# STN1170_RN-42_CPU_Rev2.net
KiCad netlist of a schematic drawn in Altium Designer
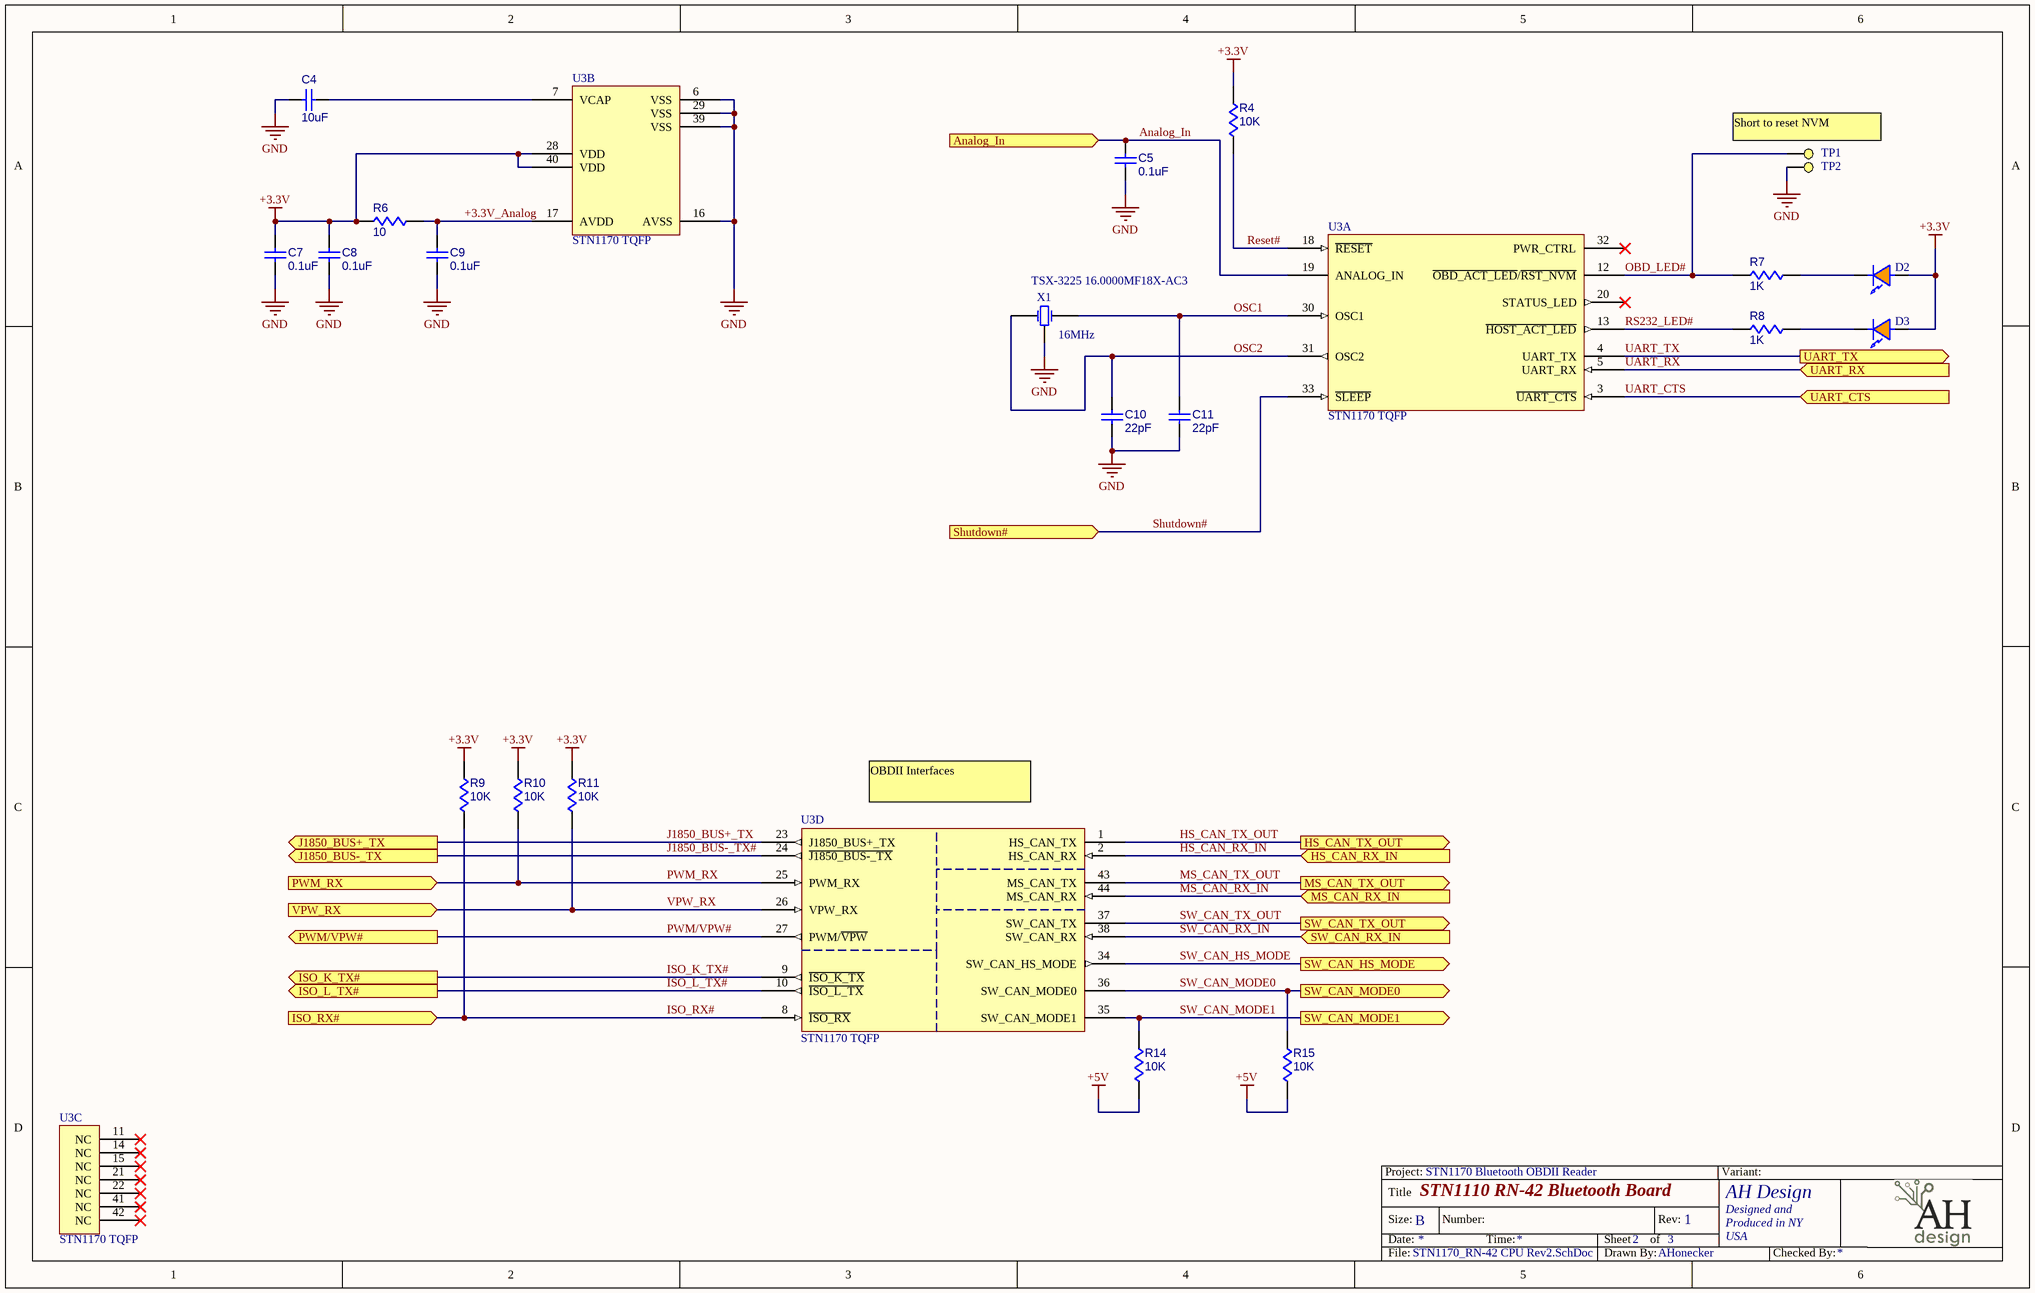
[diagram p0: STN1170_RN-42 CPU Rev2.SchDoc]

(export (version "E")
  (design (tool "Eeschema 10.0.6"))
  (components
    (comp (ref "C4")
      (value "10uF")
      (footprint "CC0805")
      (description "10uF 6.3V, in a CC0805, X5R ,+/-20%,LF")
      (fields
        (field (name "VOLTAGE") "6.3")
        (field (name "MANUFACTURER") "Kemet Electronics Corp")
        (field (name "PUBLISHER") "AltiumDBManager1.4-MWyman")
        (field (name "APPROVED") "Yes")
        (field (name "APPROVER") "IHS")
      )
      (libsource (lib "VanteonStd") (part "CAP"))
    )
    (comp (ref "C5")
      (value "0.1uF")
      (footprint "CC0603")
      (description "0.1uF 50V, in a CC0603, X7R ,+/-20%,LF")
      (fields
        (field (name "VOLTAGE") "50")
        (field (name "MANUFACTURER") "Kemet")
        (field (name "PUBLISHER") "AltiumdBManager")
        (field (name "APPROVED") "Pending")
      )
      (libsource (lib "VanteonStd") (part "CAP"))
    )
    (comp (ref "C7")
      (value "0.1uF")
      (footprint "CC0603")
      (description "0.1uF 50V, in a CC0603, X7R ,+/-20%,LF")
      (fields
        (field (name "VOLTAGE") "50")
        (field (name "MANUFACTURER") "Kemet")
        (field (name "PUBLISHER") "AltiumdBManager")
        (field (name "APPROVED") "Pending")
      )
      (libsource (lib "VanteonStd") (part "CAP"))
    )
    (comp (ref "C8")
      (value "0.1uF")
      (footprint "CC0603")
      (description "0.1uF 50V, in a CC0603, X7R ,+/-20%,LF")
      (fields
        (field (name "VOLTAGE") "50")
        (field (name "MANUFACTURER") "Kemet")
        (field (name "PUBLISHER") "AltiumdBManager")
        (field (name "APPROVED") "Pending")
      )
      (libsource (lib "VanteonStd") (part "CAP"))
    )
    (comp (ref "C9")
      (value "0.1uF")
      (footprint "CC0603")
      (description "0.1uF 50V, in a CC0603, X7R ,+/-20%,LF")
      (fields
        (field (name "VOLTAGE") "50")
        (field (name "MANUFACTURER") "Kemet")
        (field (name "PUBLISHER") "AltiumdBManager")
        (field (name "APPROVED") "Pending")
      )
      (libsource (lib "VanteonStd") (part "CAP"))
    )
    (comp (ref "C10")
      (value "22pF")
      (footprint "CC0603")
      (description "22pF 10V, in a CC0603, COG ,+/-2%,LF")
      (fields
        (field (name "VOLTAGE") "10")
        (field (name "MANUFACTURER") "Kemet Electronics Corp")
        (field (name "PUBLISHER") "AltiumDBManager1.4-MWyman")
        (field (name "APPROVED") "Yes")
        (field (name "APPROVER") "IHS")
      )
      (libsource (lib "VanteonStd") (part "CAP"))
    )
    (comp (ref "C11")
      (value "22pF")
      (footprint "CC0603")
      (description "22pF 10V, in a CC0603, COG ,+/-2%,LF")
      (fields
        (field (name "VOLTAGE") "10")
        (field (name "MANUFACTURER") "Kemet Electronics Corp")
        (field (name "PUBLISHER") "AltiumDBManager1.4-MWyman")
        (field (name "APPROVED") "Yes")
        (field (name "APPROVER") "IHS")
      )
      (libsource (lib "VanteonStd") (part "CAP"))
    )
    (comp (ref "D2")
      (value "APA1606SECK")
      (footprint "KINGBRIGHT_APA1606SECK")
      (description "LED 1.6X0.6MM 601NM Orange Right-Angle SMD")
      (fields
        (field (name "MANUFACTURER") "Kingbright Corp.")
        (field (name "APPROVED") "No")
        (field (name "PUBLISHER") "Vanteon - AHonecker")
      )
      (libsource (lib "AndyHoneckerNewComp") (part "KINGBRIGHT_APA1606SECK"))
    )
    (comp (ref "D3")
      (value "APA1606SECK")
      (footprint "KINGBRIGHT_APA1606SECK")
      (description "LED 1.6X0.6MM 601NM Orange Right-Angle SMD")
      (fields
        (field (name "MANUFACTURER") "Kingbright Corp.")
        (field (name "APPROVED") "No")
        (field (name "PUBLISHER") "Vanteon - AHonecker")
      )
      (libsource (lib "AndyHoneckerNewComp") (part "KINGBRIGHT_APA1606SECK"))
    )
    (comp (ref "R4")
      (value "10K")
      (footprint "R0603")
      (description "10K, Gen Purp Chip, R0603 0.1W 5%")
      (fields
        (field (name "MANUFACTURER") "Panasonic")
        (field (name "PARTNUMBER") "ERJ3GEYJ103V")
        (field (name "PUBLISHER") "AltiumDBManager1.1")
      )
      (libsource (lib "VanteonStd") (part "RES"))
    )
    (comp (ref "R6")
      (value "10")
      (footprint "R0603")
      (description "10, Gen Purp Chip, R0603 0.1W 5%")
      (fields
        (field (name "MANUFACTURER") "Panasonic")
        (field (name "PARTNUMBER") "ERJ3GEYJ100V")
        (field (name "PUBLISHER") "AltiumDBManager1.1")
      )
      (libsource (lib "VanteonStd") (part "RES"))
    )
    (comp (ref "R7")
      (value "1K")
      (footprint "R0603")
      (description "1K, Gen Purp Chip, R0603 0.1W 5%")
      (fields
        (field (name "MANUFACTURER") "Panasonic")
        (field (name "PARTNUMBER") "ERJ3GEYJ102V")
        (field (name "PUBLISHER") "AltiumDBManager1.1")
      )
      (libsource (lib "VanteonStd") (part "RES"))
    )
    (comp (ref "R8")
      (value "1K")
      (footprint "R0603")
      (description "1K, Gen Purp Chip, R0603 0.1W 5%")
      (fields
        (field (name "MANUFACTURER") "Panasonic")
        (field (name "PARTNUMBER") "ERJ3GEYJ102V")
        (field (name "PUBLISHER") "AltiumDBManager1.1")
      )
      (libsource (lib "VanteonStd") (part "RES"))
    )
    (comp (ref "R9")
      (value "10K")
      (footprint "R0603")
      (description "10K, Gen Purp Chip, R0603 0.1W 5%")
      (fields
        (field (name "MANUFACTURER") "Panasonic")
        (field (name "PARTNUMBER") "ERJ3GEYJ103V")
        (field (name "PUBLISHER") "AltiumDBManager1.1")
      )
      (libsource (lib "VanteonStd") (part "RES"))
    )
    (comp (ref "R10")
      (value "10K")
      (footprint "R0603")
      (description "10K, Gen Purp Chip, R0603 0.1W 5%")
      (fields
        (field (name "MANUFACTURER") "Panasonic")
        (field (name "PARTNUMBER") "ERJ3GEYJ103V")
        (field (name "PUBLISHER") "AltiumDBManager1.1")
      )
      (libsource (lib "VanteonStd") (part "RES"))
    )
    (comp (ref "R11")
      (value "10K")
      (footprint "R0603")
      (description "10K, Gen Purp Chip, R0603 0.1W 5%")
      (fields
        (field (name "MANUFACTURER") "Panasonic")
        (field (name "PARTNUMBER") "ERJ3GEYJ103V")
        (field (name "PUBLISHER") "AltiumDBManager1.1")
      )
      (libsource (lib "VanteonStd") (part "RES"))
    )
    (comp (ref "R14")
      (value "10K")
      (footprint "R0603")
      (description "10K, Gen Purp Chip, R0603 0.1W 5%")
      (fields
        (field (name "MANUFACTURER") "Panasonic")
        (field (name "PARTNUMBER") "ERJ3GEYJ103V")
        (field (name "PUBLISHER") "AltiumDBManager1.1")
      )
      (libsource (lib "VanteonStd") (part "RES"))
    )
    (comp (ref "R15")
      (value "10K")
      (footprint "R0603")
      (description "10K, Gen Purp Chip, R0603 0.1W 5%")
      (fields
        (field (name "MANUFACTURER") "Panasonic")
        (field (name "PARTNUMBER") "ERJ3GEYJ103V")
        (field (name "PUBLISHER") "AltiumDBManager1.1")
      )
      (libsource (lib "VanteonStd") (part "RES"))
    )
    (comp (ref "TP1")
      (value "~")
      (footprint "TP,0.5mmx0.5mm,RND")
      (description "0.5mm diameter testpoint")
      (libsource (lib "MISC") (part "TP, 0.5mm x 0.5mm SMT, RND"))
    )
    (comp (ref "TP2")
      (value "~")
      (footprint "TP,0.5mmx0.5mm,RND")
      (description "0.5mm diameter testpoint")
      (libsource (lib "MISC") (part "TP, 0.5mm x 0.5mm SMT, RND"))
    )
    (comp (ref "U3")
      (value "STN1170 TQFP")
      (footprint "TQFP80P1200X1200X120-44N")
      (description "Multiprotocol OBD to UART Interpreter with Medium-Speed CAN and Single-Wire CAN support")
      (fields (field (name "MANUFACTURER") "Scantool.net"))
      (libsource (lib "Andy_Parts") (part "STN1170_TQFP"))
    )
    (comp (ref "X1")
      (value "TSX-3225 16.0000MF18X-AC3")
      (footprint "Epson_TSX-3225 16.0000MF18X-AC3")
      (description "CRYSTAL 16.0000MHZ 9PF SMD")
      (fields (field (name "MANUFACTURER") "Epson") (field (name "ALTIUM_VALUE") "16MHz"))
      (libsource (lib "Andy_Parts") (part "TSX-3225 16.0000MF18X-AC3"))
    )
  )
  (nets
    (net (code "1") (name "+3.3V") (class "Default")
      (node (ref "C7") (pin "2") (pinfunction "2_2") (pintype "passive"))
      (node (ref "C8") (pin "2") (pinfunction "2_2") (pintype "passive"))
      (node (ref "D2") (pin "A") (pinfunction "A_A") (pintype "passive"))
      (node (ref "D3") (pin "A") (pinfunction "A_A") (pintype "passive"))
      (node (ref "R10") (pin "1") (pinfunction "1_1") (pintype "passive"))
      (node (ref "R11") (pin "1") (pinfunction "1_1") (pintype "passive"))
      (node (ref "R4") (pin "1") (pinfunction "1_1") (pintype "passive"))
      (node (ref "R6") (pin "1") (pinfunction "1_1") (pintype "passive"))
      (node (ref "R9") (pin "1") (pinfunction "1_1") (pintype "passive"))
      (node (ref "U3") (pin "28") (pinfunction "VDD_28") (pintype "power_in"))
      (node (ref "U3") (pin "40") (pinfunction "VDD_40") (pintype "power_in"))
    )
    (net (code "2") (name "+5V") (class "Default")
      (node (ref "R14") (pin "2") (pinfunction "2_2") (pintype "passive"))
      (node (ref "R15") (pin "2") (pinfunction "2_2") (pintype "passive"))
    )
    (net (code "3") (name "/+3.3V_Analog") (class "Default")
      (node (ref "C9") (pin "2") (pinfunction "2_2") (pintype "passive"))
      (node (ref "R6") (pin "2") (pinfunction "2_2") (pintype "passive"))
      (node (ref "U3") (pin "17") (pinfunction "AVDD_17") (pintype "power_in"))
    )
    (net (code "4") (name "/Analog_In") (class "Default")
      (node (ref "C5") (pin "2") (pinfunction "2_2") (pintype "passive"))
      (node (ref "U3") (pin "19") (pinfunction "ANALOG_IN_19") (pintype "passive"))
    )
    (net (code "5") (name "/HS_CAN_RX_IN") (class "Default")
      (node (ref "U3") (pin "2") (pinfunction "HS_CAN_RX_2") (pintype "input"))
    )
    (net (code "6") (name "/HS_CAN_TX_OUT") (class "Default")
      (node (ref "U3") (pin "1") (pinfunction "HS_CAN_TX_1") (pintype "open_collector"))
    )
    (net (code "7") (name "/ISO_K_TX#") (class "Default")
      (node (ref "U3") (pin "9") (pinfunction "~{ISO_K_TX}_9") (pintype "output"))
    )
    (net (code "8") (name "/ISO_L_TX#") (class "Default")
      (node (ref "U3") (pin "10") (pinfunction "~{ISO_L_TX}_10") (pintype "output"))
    )
    (net (code "9") (name "/ISO_RX#") (class "Default")
      (node (ref "R9") (pin "2") (pinfunction "2_2") (pintype "passive"))
      (node (ref "U3") (pin "8") (pinfunction "~{ISO_RX}_8") (pintype "input"))
    )
    (net (code "10") (name "/J1850_BUS+_TX") (class "Default")
      (node (ref "U3") (pin "23") (pinfunction "J1850_BUS+_TX_23") (pintype "output"))
    )
    (net (code "11") (name "/J1850_BUS-_TX#") (class "Default")
      (node (ref "U3") (pin "24") (pinfunction "~{J1850_BUS-_TX}_24") (pintype "output"))
    )
    (net (code "12") (name "/MS_CAN_RX_IN") (class "Default")
      (node (ref "U3") (pin "44") (pinfunction "MS_CAN_RX_44") (pintype "input"))
    )
    (net (code "13") (name "/MS_CAN_TX_OUT") (class "Default")
      (node (ref "U3") (pin "43") (pinfunction "MS_CAN_TX_43") (pintype "open_collector"))
    )
    (net (code "14") (name "/OBD_LED#") (class "Default")
      (node (ref "R7") (pin "1") (pinfunction "1_1") (pintype "passive"))
      (node (ref "TP1") (pin "1") (pinfunction "TP_1") (pintype "passive"))
      (node (ref "U3") (pin "12") (pinfunction "~{OBD_ACT_LED}/~{RST_NVM}_12") (pintype "open_collector"))
    )
    (net (code "15") (name "/OSC1") (class "Default")
      (node (ref "C11") (pin "2") (pinfunction "2_2") (pintype "passive"))
      (node (ref "U3") (pin "30") (pinfunction "OSC1_30") (pintype "input"))
      (node (ref "X1") (pin "3") (pinfunction "OSC2_3") (pintype "passive"))
    )
    (net (code "16") (name "/OSC2") (class "Default")
      (node (ref "C10") (pin "2") (pinfunction "2_2") (pintype "passive"))
      (node (ref "U3") (pin "31") (pinfunction "OSC2_31") (pintype "output"))
      (node (ref "X1") (pin "1") (pinfunction "OSC1_1") (pintype "passive"))
    )
    (net (code "17") (name "/PWM_RX") (class "Default")
      (node (ref "R10") (pin "2") (pinfunction "2_2") (pintype "passive"))
      (node (ref "U3") (pin "25") (pinfunction "PWM_RX_25") (pintype "input"))
    )
    (net (code "18") (name "/PWM{slash}VPW#") (class "Default")
      (node (ref "U3") (pin "27") (pinfunction "PWM/~{VPW}_27") (pintype "output"))
    )
    (net (code "19") (name "/RS232_LED#") (class "Default")
      (node (ref "R8") (pin "1") (pinfunction "1_1") (pintype "passive"))
      (node (ref "U3") (pin "13") (pinfunction "~{HOST_ACT_LED}_13") (pintype "output"))
    )
    (net (code "20") (name "/Reset#") (class "Default")
      (node (ref "R4") (pin "2") (pinfunction "2_2") (pintype "passive"))
      (node (ref "U3") (pin "18") (pinfunction "~{RESET}_18") (pintype "input"))
    )
    (net (code "21") (name "/SW_CAN_HS_MODE") (class "Default")
      (node (ref "U3") (pin "34") (pinfunction "SW_CAN_HS_MODE_34") (pintype "output"))
    )
    (net (code "22") (name "/SW_CAN_MODE0") (class "Default")
      (node (ref "R15") (pin "1") (pinfunction "1_1") (pintype "passive"))
      (node (ref "U3") (pin "36") (pinfunction "SW_CAN_MODE0_36") (pintype "open_collector"))
    )
    (net (code "23") (name "/SW_CAN_MODE1") (class "Default")
      (node (ref "R14") (pin "1") (pinfunction "1_1") (pintype "passive"))
      (node (ref "U3") (pin "35") (pinfunction "SW_CAN_MODE1_35") (pintype "open_collector"))
    )
    (net (code "24") (name "/SW_CAN_RX_IN") (class "Default")
      (node (ref "U3") (pin "38") (pinfunction "SW_CAN_RX_38") (pintype "input"))
    )
    (net (code "25") (name "/SW_CAN_TX_OUT") (class "Default")
      (node (ref "U3") (pin "37") (pinfunction "SW_CAN_TX_37") (pintype "open_collector"))
    )
    (net (code "26") (name "/Shutdown#") (class "Default")
      (node (ref "U3") (pin "33") (pinfunction "~{SLEEP}_33") (pintype "input"))
    )
    (net (code "27") (name "/UART_CTS") (class "Default")
      (node (ref "U3") (pin "3") (pinfunction "~{UART_CTS}_3") (pintype "input"))
    )
    (net (code "28") (name "/UART_RX") (class "Default")
      (node (ref "U3") (pin "5") (pinfunction "UART_RX_5") (pintype "input"))
    )
    (net (code "29") (name "/UART_TX") (class "Default")
      (node (ref "U3") (pin "4") (pinfunction "UART_TX_4") (pintype "open_collector"))
    )
    (net (code "30") (name "/VPW_RX") (class "Default")
      (node (ref "R11") (pin "2") (pinfunction "2_2") (pintype "passive"))
      (node (ref "U3") (pin "26") (pinfunction "VPW_RX_26") (pintype "input"))
    )
    (net (code "31") (name "GND") (class "Default")
      (node (ref "C10") (pin "1") (pinfunction "1_1") (pintype "passive"))
      (node (ref "C11") (pin "1") (pinfunction "1_1") (pintype "passive"))
      (node (ref "C4") (pin "2") (pinfunction "2_2") (pintype "passive"))
      (node (ref "C5") (pin "1") (pinfunction "1_1") (pintype "passive"))
      (node (ref "C7") (pin "1") (pinfunction "1_1") (pintype "passive"))
      (node (ref "C8") (pin "1") (pinfunction "1_1") (pintype "passive"))
      (node (ref "C9") (pin "1") (pinfunction "1_1") (pintype "passive"))
      (node (ref "TP2") (pin "1") (pinfunction "TP_1") (pintype "passive"))
      (node (ref "U3") (pin "16") (pinfunction "AVSS_16") (pintype "power_in"))
      (node (ref "U3") (pin "29") (pinfunction "VSS_29") (pintype "power_in"))
      (node (ref "U3") (pin "39") (pinfunction "VSS_39") (pintype "power_in"))
      (node (ref "U3") (pin "6") (pinfunction "VSS_6") (pintype "power_in"))
      (node (ref "X1") (pin "GND") (pinfunction "GND_GND") (pintype "power_in"))
    )
    (net (code "32") (name "Net-(D2-PadC)") (class "Default")
      (node (ref "D2") (pin "C") (pinfunction "C_C") (pintype "passive"))
      (node (ref "R7") (pin "2") (pinfunction "2_2") (pintype "passive"))
    )
    (net (code "33") (name "Net-(D3-PadC)") (class "Default")
      (node (ref "D3") (pin "C") (pinfunction "C_C") (pintype "passive"))
      (node (ref "R8") (pin "2") (pinfunction "2_2") (pintype "passive"))
    )
    (net (code "34") (name "Net-(U3B-VCAP)") (class "Default")
      (node (ref "C4") (pin "1") (pinfunction "1_1") (pintype "passive"))
      (node (ref "U3") (pin "7") (pinfunction "VCAP_7") (pintype "power_in"))
    )
    (net (code "35") (name "unconnected-(U3A-PWR_CTRL-Pad32)") (class "Default")
      (node (ref "U3") (pin "32") (pinfunction "PWR_CTRL_32") (pintype "open_collector+no_connect"))
    )
    (net (code "36") (name "unconnected-(U3A-STATUS_LED-Pad20)") (class "Default")
      (node (ref "U3") (pin "20") (pinfunction "STATUS_LED_20") (pintype "output+no_connect"))
    )
    (net (code "37") (name "unconnected-(U3C-NC-Pad11)") (class "Default")
      (node (ref "U3") (pin "11") (pinfunction "NC_11") (pintype "passive+no_connect"))
    )
    (net (code "38") (name "unconnected-(U3C-NC-Pad14)") (class "Default")
      (node (ref "U3") (pin "14") (pinfunction "NC_14") (pintype "passive+no_connect"))
    )
    (net (code "39") (name "unconnected-(U3C-NC-Pad15)") (class "Default")
      (node (ref "U3") (pin "15") (pinfunction "NC_15") (pintype "passive+no_connect"))
    )
    (net (code "40") (name "unconnected-(U3C-NC-Pad21)") (class "Default")
      (node (ref "U3") (pin "21") (pinfunction "NC_21") (pintype "passive+no_connect"))
    )
    (net (code "41") (name "unconnected-(U3C-NC-Pad22)") (class "Default")
      (node (ref "U3") (pin "22") (pinfunction "NC_22") (pintype "passive+no_connect"))
    )
    (net (code "42") (name "unconnected-(U3C-NC-Pad41)") (class "Default")
      (node (ref "U3") (pin "41") (pinfunction "NC_41") (pintype "passive+no_connect"))
    )
    (net (code "43") (name "unconnected-(U3C-NC-Pad42)") (class "Default")
      (node (ref "U3") (pin "42") (pinfunction "NC_42") (pintype "passive+no_connect"))
    )
  )
)
